# Module_Output_Sockets.net
KiCad netlist of a schematic drawn in Altium Designer
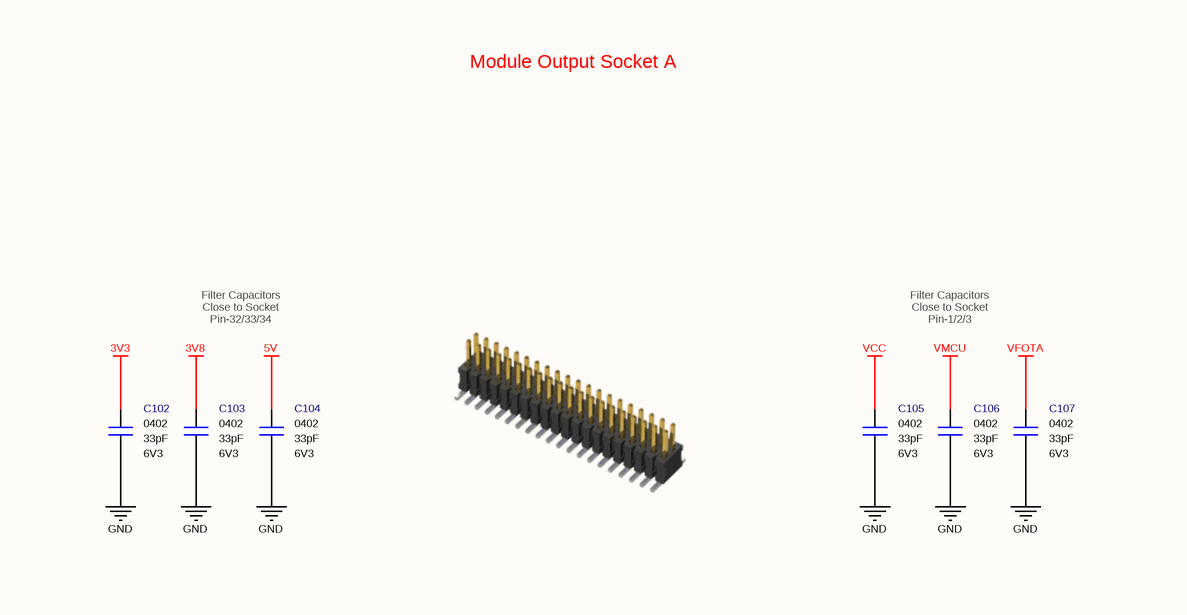
[diagram p0: Module Output Sockets.SchDoc, top left]
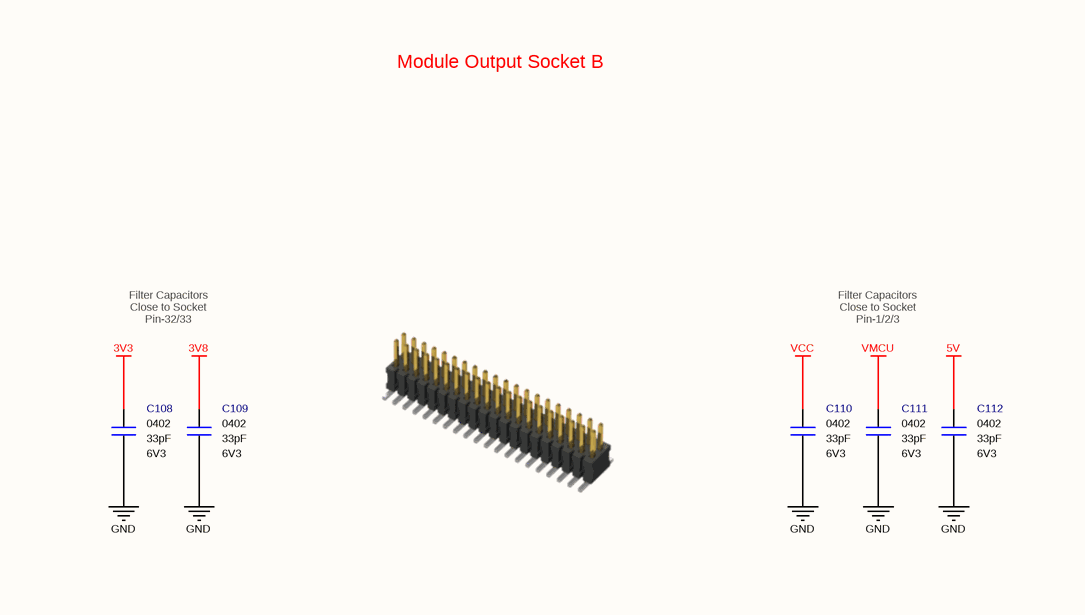
[diagram p1: Module Output Sockets.SchDoc, top right]
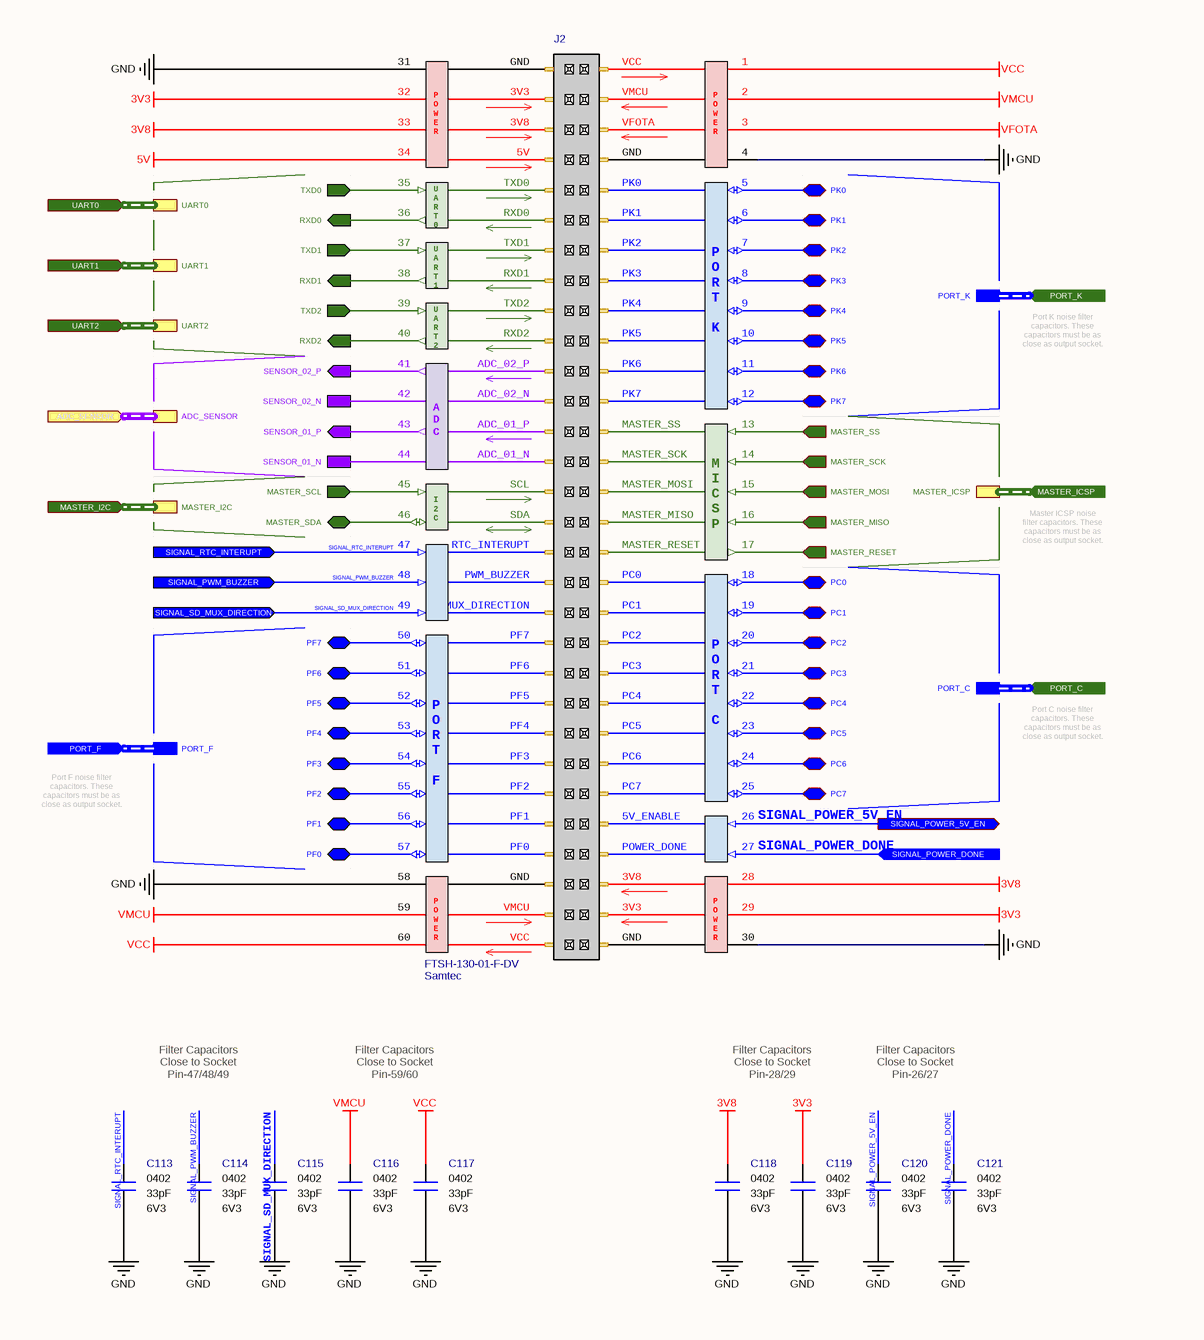
[diagram p2: Module Output Sockets.SchDoc, bottom left]
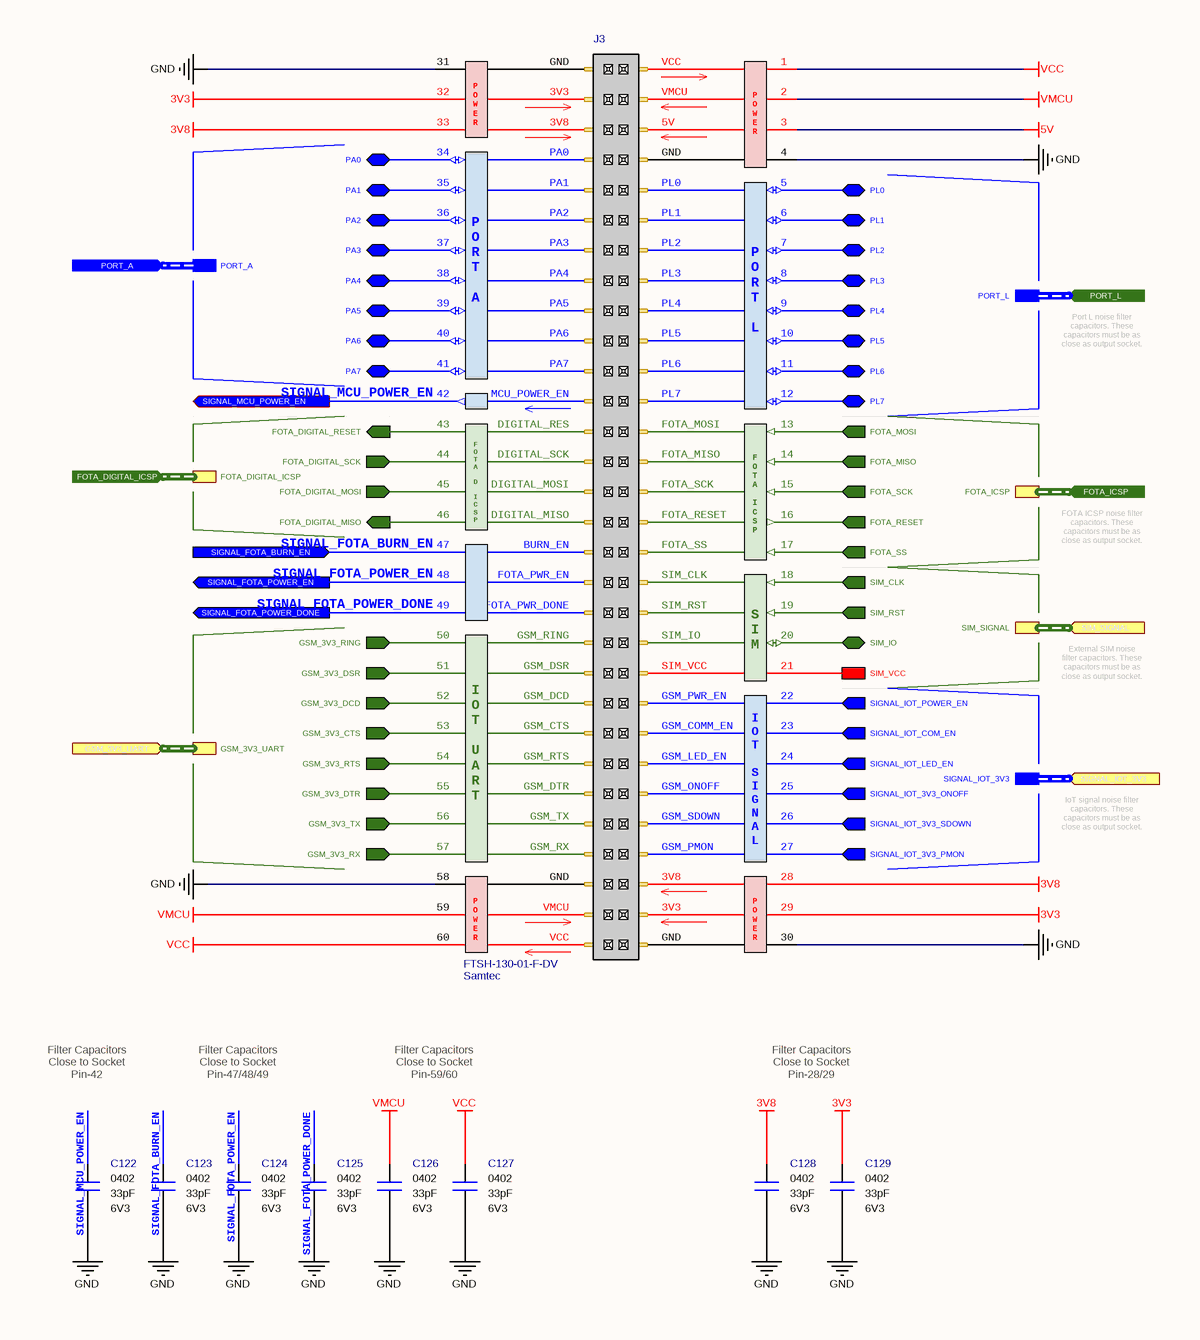
[diagram p3: Module Output Sockets.SchDoc, bottom right]

(export (version "E")
  (design (tool "Eeschema 10.0.6"))
  (components
    (comp (ref "C102")
      (value "33pF")
      (footprint "CAPACITOR_0402")
      (description "Capacitor - 33pF [0402] (Ceramic)")
      (fields
        (field (name "TOLERANCE") "10%")
        (field (name "CASE") "0402")
        (field (name "VOLTAGE") "6V3")
        (field (name "MANUFACTURER PART NUMBER") "C0402C330J9RACAUTO")
      )
      (libsource (lib "Ovoo_Library") (part "Capacitor - 33pF [0402-6V3]"))
    )
    (comp (ref "C103")
      (value "33pF")
      (footprint "CAPACITOR_0402")
      (description "Capacitor - 33pF [0402] (Ceramic)")
      (fields
        (field (name "TOLERANCE") "10%")
        (field (name "CASE") "0402")
        (field (name "VOLTAGE") "6V3")
        (field (name "MANUFACTURER PART NUMBER") "C0402C330J9RACAUTO")
      )
      (libsource (lib "Ovoo_Library") (part "Capacitor - 33pF [0402-6V3]"))
    )
    (comp (ref "C104")
      (value "33pF")
      (footprint "CAPACITOR_0402")
      (description "Capacitor - 33pF [0402] (Ceramic)")
      (fields
        (field (name "TOLERANCE") "10%")
        (field (name "CASE") "0402")
        (field (name "VOLTAGE") "6V3")
        (field (name "MANUFACTURER PART NUMBER") "C0402C330J9RACAUTO")
      )
      (libsource (lib "Ovoo_Library") (part "Capacitor - 33pF [0402-6V3]"))
    )
    (comp (ref "C105")
      (value "33pF")
      (footprint "CAPACITOR_0402")
      (description "Capacitor - 33pF [0402] (Ceramic)")
      (fields
        (field (name "TOLERANCE") "10%")
        (field (name "CASE") "0402")
        (field (name "VOLTAGE") "6V3")
        (field (name "MANUFACTURER PART NUMBER") "C0402C330J9RACAUTO")
      )
      (libsource (lib "Ovoo_Library") (part "Capacitor - 33pF [0402-6V3]"))
    )
    (comp (ref "C106")
      (value "33pF")
      (footprint "CAPACITOR_0402")
      (description "Capacitor - 33pF [0402] (Ceramic)")
      (fields
        (field (name "TOLERANCE") "10%")
        (field (name "CASE") "0402")
        (field (name "VOLTAGE") "6V3")
        (field (name "MANUFACTURER PART NUMBER") "C0402C330J9RACAUTO")
      )
      (libsource (lib "Ovoo_Library") (part "Capacitor - 33pF [0402-6V3]"))
    )
    (comp (ref "C107")
      (value "33pF")
      (footprint "CAPACITOR_0402")
      (description "Capacitor - 33pF [0402] (Ceramic)")
      (fields
        (field (name "TOLERANCE") "10%")
        (field (name "CASE") "0402")
        (field (name "VOLTAGE") "6V3")
        (field (name "MANUFACTURER PART NUMBER") "C0402C330J9RACAUTO")
      )
      (libsource (lib "Ovoo_Library") (part "Capacitor - 33pF [0402-6V3]"))
    )
    (comp (ref "C108")
      (value "33pF")
      (footprint "CAPACITOR_0402")
      (description "Capacitor - 33pF [0402] (Ceramic)")
      (fields
        (field (name "TOLERANCE") "10%")
        (field (name "CASE") "0402")
        (field (name "VOLTAGE") "6V3")
        (field (name "MANUFACTURER PART NUMBER") "C0402C330J9RACAUTO")
      )
      (libsource (lib "Ovoo_Library") (part "Capacitor - 33pF [0402-6V3]"))
    )
    (comp (ref "C109")
      (value "33pF")
      (footprint "CAPACITOR_0402")
      (description "Capacitor - 33pF [0402] (Ceramic)")
      (fields
        (field (name "TOLERANCE") "10%")
        (field (name "CASE") "0402")
        (field (name "VOLTAGE") "6V3")
        (field (name "MANUFACTURER PART NUMBER") "C0402C330J9RACAUTO")
      )
      (libsource (lib "Ovoo_Library") (part "Capacitor - 33pF [0402-6V3]"))
    )
    (comp (ref "C110")
      (value "33pF")
      (footprint "CAPACITOR_0402")
      (description "Capacitor - 33pF [0402] (Ceramic)")
      (fields
        (field (name "TOLERANCE") "10%")
        (field (name "CASE") "0402")
        (field (name "VOLTAGE") "6V3")
        (field (name "MANUFACTURER PART NUMBER") "C0402C330J9RACAUTO")
      )
      (libsource (lib "Ovoo_Library") (part "Capacitor - 33pF [0402-6V3]"))
    )
    (comp (ref "C111")
      (value "33pF")
      (footprint "CAPACITOR_0402")
      (description "Capacitor - 33pF [0402] (Ceramic)")
      (fields
        (field (name "TOLERANCE") "10%")
        (field (name "CASE") "0402")
        (field (name "VOLTAGE") "6V3")
        (field (name "MANUFACTURER PART NUMBER") "C0402C330J9RACAUTO")
      )
      (libsource (lib "Ovoo_Library") (part "Capacitor - 33pF [0402-6V3]"))
    )
    (comp (ref "C112")
      (value "33pF")
      (footprint "CAPACITOR_0402")
      (description "Capacitor - 33pF [0402] (Ceramic)")
      (fields
        (field (name "TOLERANCE") "10%")
        (field (name "CASE") "0402")
        (field (name "VOLTAGE") "6V3")
        (field (name "MANUFACTURER PART NUMBER") "C0402C330J9RACAUTO")
      )
      (libsource (lib "Ovoo_Library") (part "Capacitor - 33pF [0402-6V3]"))
    )
    (comp (ref "C113")
      (value "33pF")
      (footprint "CAPACITOR_0402")
      (description "Capacitor - 33pF [0402] (Ceramic)")
      (fields
        (field (name "TOLERANCE") "10%")
        (field (name "CASE") "0402")
        (field (name "VOLTAGE") "6V3")
        (field (name "MANUFACTURER PART NUMBER") "C0402C330J9RACAUTO")
      )
      (libsource (lib "Ovoo_Library") (part "Capacitor - 33pF [0402-6V3]"))
    )
    (comp (ref "C114")
      (value "33pF")
      (footprint "CAPACITOR_0402")
      (description "Capacitor - 33pF [0402] (Ceramic)")
      (fields
        (field (name "TOLERANCE") "10%")
        (field (name "CASE") "0402")
        (field (name "VOLTAGE") "6V3")
        (field (name "MANUFACTURER PART NUMBER") "C0402C330J9RACAUTO")
      )
      (libsource (lib "Ovoo_Library") (part "Capacitor - 33pF [0402-6V3]"))
    )
    (comp (ref "C115")
      (value "33pF")
      (footprint "CAPACITOR_0402")
      (description "Capacitor - 33pF [0402] (Ceramic)")
      (fields
        (field (name "TOLERANCE") "10%")
        (field (name "CASE") "0402")
        (field (name "VOLTAGE") "6V3")
        (field (name "MANUFACTURER PART NUMBER") "C0402C330J9RACAUTO")
      )
      (libsource (lib "Ovoo_Library") (part "Capacitor - 33pF [0402-6V3]"))
    )
    (comp (ref "C116")
      (value "33pF")
      (footprint "CAPACITOR_0402")
      (description "Capacitor - 33pF [0402] (Ceramic)")
      (fields
        (field (name "TOLERANCE") "10%")
        (field (name "CASE") "0402")
        (field (name "VOLTAGE") "6V3")
        (field (name "MANUFACTURER PART NUMBER") "C0402C330J9RACAUTO")
      )
      (libsource (lib "Ovoo_Library") (part "Capacitor - 33pF [0402-6V3]"))
    )
    (comp (ref "C117")
      (value "33pF")
      (footprint "CAPACITOR_0402")
      (description "Capacitor - 33pF [0402] (Ceramic)")
      (fields
        (field (name "TOLERANCE") "10%")
        (field (name "CASE") "0402")
        (field (name "VOLTAGE") "6V3")
        (field (name "MANUFACTURER PART NUMBER") "C0402C330J9RACAUTO")
      )
      (libsource (lib "Ovoo_Library") (part "Capacitor - 33pF [0402-6V3]"))
    )
    (comp (ref "C118")
      (value "33pF")
      (footprint "CAPACITOR_0402")
      (description "Capacitor - 33pF [0402] (Ceramic)")
      (fields
        (field (name "TOLERANCE") "10%")
        (field (name "CASE") "0402")
        (field (name "VOLTAGE") "6V3")
        (field (name "MANUFACTURER PART NUMBER") "C0402C330J9RACAUTO")
      )
      (libsource (lib "Ovoo_Library") (part "Capacitor - 33pF [0402-6V3]"))
    )
    (comp (ref "C119")
      (value "33pF")
      (footprint "CAPACITOR_0402")
      (description "Capacitor - 33pF [0402] (Ceramic)")
      (fields
        (field (name "TOLERANCE") "10%")
        (field (name "CASE") "0402")
        (field (name "VOLTAGE") "6V3")
        (field (name "MANUFACTURER PART NUMBER") "C0402C330J9RACAUTO")
      )
      (libsource (lib "Ovoo_Library") (part "Capacitor - 33pF [0402-6V3]"))
    )
    (comp (ref "C120")
      (value "33pF")
      (footprint "CAPACITOR_0402")
      (description "Capacitor - 33pF [0402] (Ceramic)")
      (fields
        (field (name "TOLERANCE") "10%")
        (field (name "CASE") "0402")
        (field (name "VOLTAGE") "6V3")
        (field (name "MANUFACTURER PART NUMBER") "C0402C330J9RACAUTO")
      )
      (libsource (lib "Ovoo_Library") (part "Capacitor - 33pF [0402-6V3]"))
    )
    (comp (ref "C121")
      (value "33pF")
      (footprint "CAPACITOR_0402")
      (description "Capacitor - 33pF [0402] (Ceramic)")
      (fields
        (field (name "TOLERANCE") "10%")
        (field (name "CASE") "0402")
        (field (name "VOLTAGE") "6V3")
        (field (name "MANUFACTURER PART NUMBER") "C0402C330J9RACAUTO")
      )
      (libsource (lib "Ovoo_Library") (part "Capacitor - 33pF [0402-6V3]"))
    )
    (comp (ref "C122")
      (value "33pF")
      (footprint "CAPACITOR_0402")
      (description "Capacitor - 33pF [0402] (Ceramic)")
      (fields
        (field (name "TOLERANCE") "10%")
        (field (name "CASE") "0402")
        (field (name "VOLTAGE") "6V3")
        (field (name "MANUFACTURER PART NUMBER") "C0402C330J9RACAUTO")
      )
      (libsource (lib "Ovoo_Library") (part "Capacitor - 33pF [0402-6V3]"))
    )
    (comp (ref "C123")
      (value "33pF")
      (footprint "CAPACITOR_0402")
      (description "Capacitor - 33pF [0402] (Ceramic)")
      (fields
        (field (name "TOLERANCE") "10%")
        (field (name "CASE") "0402")
        (field (name "VOLTAGE") "6V3")
        (field (name "MANUFACTURER PART NUMBER") "C0402C330J9RACAUTO")
      )
      (libsource (lib "Ovoo_Library") (part "Capacitor - 33pF [0402-6V3]"))
    )
    (comp (ref "C124")
      (value "33pF")
      (footprint "CAPACITOR_0402")
      (description "Capacitor - 33pF [0402] (Ceramic)")
      (fields
        (field (name "TOLERANCE") "10%")
        (field (name "CASE") "0402")
        (field (name "VOLTAGE") "6V3")
        (field (name "MANUFACTURER PART NUMBER") "C0402C330J9RACAUTO")
      )
      (libsource (lib "Ovoo_Library") (part "Capacitor - 33pF [0402-6V3]"))
    )
    (comp (ref "C125")
      (value "33pF")
      (footprint "CAPACITOR_0402")
      (description "Capacitor - 33pF [0402] (Ceramic)")
      (fields
        (field (name "TOLERANCE") "10%")
        (field (name "CASE") "0402")
        (field (name "VOLTAGE") "6V3")
        (field (name "MANUFACTURER PART NUMBER") "C0402C330J9RACAUTO")
      )
      (libsource (lib "Ovoo_Library") (part "Capacitor - 33pF [0402-6V3]"))
    )
    (comp (ref "C126")
      (value "33pF")
      (footprint "CAPACITOR_0402")
      (description "Capacitor - 33pF [0402] (Ceramic)")
      (fields
        (field (name "TOLERANCE") "10%")
        (field (name "CASE") "0402")
        (field (name "VOLTAGE") "6V3")
        (field (name "MANUFACTURER PART NUMBER") "C0402C330J9RACAUTO")
      )
      (libsource (lib "Ovoo_Library") (part "Capacitor - 33pF [0402-6V3]"))
    )
    (comp (ref "C127")
      (value "33pF")
      (footprint "CAPACITOR_0402")
      (description "Capacitor - 33pF [0402] (Ceramic)")
      (fields
        (field (name "TOLERANCE") "10%")
        (field (name "CASE") "0402")
        (field (name "VOLTAGE") "6V3")
        (field (name "MANUFACTURER PART NUMBER") "C0402C330J9RACAUTO")
      )
      (libsource (lib "Ovoo_Library") (part "Capacitor - 33pF [0402-6V3]"))
    )
    (comp (ref "C128")
      (value "33pF")
      (footprint "CAPACITOR_0402")
      (description "Capacitor - 33pF [0402] (Ceramic)")
      (fields
        (field (name "TOLERANCE") "10%")
        (field (name "CASE") "0402")
        (field (name "VOLTAGE") "6V3")
        (field (name "MANUFACTURER PART NUMBER") "C0402C330J9RACAUTO")
      )
      (libsource (lib "Ovoo_Library") (part "Capacitor - 33pF [0402-6V3]"))
    )
    (comp (ref "C129")
      (value "33pF")
      (footprint "CAPACITOR_0402")
      (description "Capacitor - 33pF [0402] (Ceramic)")
      (fields
        (field (name "TOLERANCE") "10%")
        (field (name "CASE") "0402")
        (field (name "VOLTAGE") "6V3")
        (field (name "MANUFACTURER PART NUMBER") "C0402C330J9RACAUTO")
      )
      (libsource (lib "Ovoo_Library") (part "Capacitor - 33pF [0402-6V3]"))
    )
    (comp (ref "J2")
      (value "1.27 mm Pitch 2x30P Male Connector")
      (footprint "SAMTEC-FTSH-130-01-X-DV")
      (description "Headers & Wire Housings BREAKAWAY HDR VERT 6")
      (fields
        (field (name "MOUSER PART NUMBER") "200-FTSH13001FDV")
        (field (name "MANUFACTURER PART NUMBER") "FTSH-130-01-F-DV")
        (field (name "MANUFACTURER NAME") "Samtec")
      )
      (libsource (lib "Ovoo_Library") (part "Connector - B100 Male Socket [A]"))
    )
    (comp (ref "J3")
      (value "1.27 mm Pitch 2x30P Male Connector")
      (footprint "SAMTEC-FTSH-130-01-X-DV")
      (description "Headers & Wire Housings BREAKAWAY HDR VERT 6")
      (fields
        (field (name "MOUSER PART NUMBER") "200-FTSH13001FDV")
        (field (name "MANUFACTURER PART NUMBER") "FTSH-130-01-F-DV")
        (field (name "MANUFACTURER NAME") "Samtec")
      )
      (libsource (lib "Ovoo_Library") (part "Connector - B100 Male Socket [B]"))
    )
  )
  (nets
    (net (code "19") (name "/FOTA_DIGITAL_MISO") (class "Default")
      (node (ref "J3") (pin "46") (pinfunction "Pin-46_46") (pintype "passive"))
    )
    (net (code "20") (name "/FOTA_DIGITAL_MOSI") (class "Default")
      (node (ref "J3") (pin "45") (pinfunction "Pin-45_45") (pintype "passive"))
    )
    (net (code "21") (name "/FOTA_DIGITAL_RESET") (class "Default")
      (node (ref "J3") (pin "43") (pinfunction "Pin-43_43") (pintype "passive"))
    )
    (net (code "22") (name "/FOTA_DIGITAL_SCK") (class "Default")
      (node (ref "J3") (pin "44") (pinfunction "Pin-44_44") (pintype "passive"))
    )
    (net (code "24") (name "/FOTA_MISO") (class "Default")
      (node (ref "J3") (pin "14") (pinfunction "Pin-14_14") (pintype "input"))
    )
    (net (code "25") (name "/FOTA_MOSI") (class "Default")
      (node (ref "J3") (pin "13") (pinfunction "Pin-13_13") (pintype "input"))
    )
    (net (code "26") (name "/FOTA_RESET") (class "Default")
      (node (ref "J3") (pin "16") (pinfunction "Pin-16_16") (pintype "output"))
    )
    (net (code "27") (name "/FOTA_SCK") (class "Default")
      (node (ref "J3") (pin "15") (pinfunction "Pin-15_15") (pintype "input"))
    )
    (net (code "28") (name "/FOTA_SS") (class "Default")
      (node (ref "J3") (pin "17") (pinfunction "Pin-17_17") (pintype "input"))
    )
    (net (code "29") (name "/GSM_3V3_CTS") (class "Default")
      (node (ref "J3") (pin "53") (pinfunction "Pin-53_53") (pintype "passive"))
    )
    (net (code "30") (name "/GSM_3V3_DCD") (class "Default")
      (node (ref "J3") (pin "52") (pinfunction "Pin-52_52") (pintype "passive"))
    )
    (net (code "31") (name "/GSM_3V3_DSR") (class "Default")
      (node (ref "J3") (pin "51") (pinfunction "Pin-51_51") (pintype "passive"))
    )
    (net (code "32") (name "/GSM_3V3_DTR") (class "Default")
      (node (ref "J3") (pin "55") (pinfunction "Pin-55_55") (pintype "passive"))
    )
    (net (code "33") (name "/GSM_3V3_RING") (class "Default")
      (node (ref "J3") (pin "50") (pinfunction "Pin-50_50") (pintype "passive"))
    )
    (net (code "34") (name "/GSM_3V3_RTS") (class "Default")
      (node (ref "J3") (pin "54") (pinfunction "Pin-54_54") (pintype "passive"))
    )
    (net (code "35") (name "/GSM_3V3_RX") (class "Default")
      (node (ref "J3") (pin "57") (pinfunction "Pin-57_57") (pintype "passive"))
    )
    (net (code "36") (name "/GSM_3V3_TX") (class "Default")
      (node (ref "J3") (pin "56") (pinfunction "Pin-56_56") (pintype "passive"))
    )
    (net (code "40") (name "/MASTER_MISO") (class "Default")
      (node (ref "J2") (pin "16") (pinfunction "Pin-16_16") (pintype "input"))
    )
    (net (code "41") (name "/MASTER_MOSI") (class "Default")
      (node (ref "J2") (pin "15") (pinfunction "Pin-15_15") (pintype "input"))
    )
    (net (code "42") (name "/MASTER_RESET") (class "Default")
      (node (ref "J2") (pin "17") (pinfunction "Pin-17_17") (pintype "output"))
    )
    (net (code "43") (name "/MASTER_SCK") (class "Default")
      (node (ref "J2") (pin "14") (pinfunction "Pin-14_14") (pintype "input"))
    )
    (net (code "44") (name "/MASTER_SCL") (class "Default")
      (node (ref "J2") (pin "45") (pinfunction "Pin-45_45") (pintype "input"))
    )
    (net (code "45") (name "/MASTER_SDA") (class "Default")
      (node (ref "J2") (pin "46") (pinfunction "Pin-46_46") (pintype "bidirectional"))
    )
    (net (code "46") (name "/MASTER_SS") (class "Default")
      (node (ref "J2") (pin "13") (pinfunction "Pin-13_13") (pintype "input"))
    )
    (net (code "47") (name "/PA0") (class "Default")
      (node (ref "J3") (pin "34") (pinfunction "Pin-34_34") (pintype "bidirectional"))
    )
    (net (code "48") (name "/PA1") (class "Default")
      (node (ref "J3") (pin "35") (pinfunction "Pin-35_35") (pintype "bidirectional"))
    )
    (net (code "49") (name "/PA2") (class "Default")
      (node (ref "J3") (pin "36") (pinfunction "Pin-36_36") (pintype "bidirectional"))
    )
    (net (code "50") (name "/PA3") (class "Default")
      (node (ref "J3") (pin "37") (pinfunction "Pin-37_37") (pintype "bidirectional"))
    )
    (net (code "51") (name "/PA4") (class "Default")
      (node (ref "J3") (pin "38") (pinfunction "Pin-38_38") (pintype "bidirectional"))
    )
    (net (code "52") (name "/PA5") (class "Default")
      (node (ref "J3") (pin "39") (pinfunction "Pin-39_39") (pintype "bidirectional"))
    )
    (net (code "53") (name "/PA6") (class "Default")
      (node (ref "J3") (pin "40") (pinfunction "Pin-40_40") (pintype "bidirectional"))
    )
    (net (code "54") (name "/PA7") (class "Default")
      (node (ref "J3") (pin "41") (pinfunction "Pin-41_41") (pintype "bidirectional"))
    )
    (net (code "55") (name "/PC0") (class "Default")
      (node (ref "J2") (pin "18") (pinfunction "Pin-18_18") (pintype "bidirectional"))
    )
    (net (code "56") (name "/PC1") (class "Default")
      (node (ref "J2") (pin "19") (pinfunction "Pin-19_19") (pintype "bidirectional"))
    )
    (net (code "57") (name "/PC2") (class "Default")
      (node (ref "J2") (pin "20") (pinfunction "Pin-20_20") (pintype "bidirectional"))
    )
    (net (code "58") (name "/PC3") (class "Default")
      (node (ref "J2") (pin "21") (pinfunction "Pin-21_21") (pintype "bidirectional"))
    )
    (net (code "59") (name "/PC4") (class "Default")
      (node (ref "J2") (pin "22") (pinfunction "Pin-22_22") (pintype "bidirectional"))
    )
    (net (code "60") (name "/PC5") (class "Default")
      (node (ref "J2") (pin "23") (pinfunction "Pin-23_23") (pintype "bidirectional"))
    )
    (net (code "61") (name "/PC6") (class "Default")
      (node (ref "J2") (pin "24") (pinfunction "Pin-24_24") (pintype "bidirectional"))
    )
    (net (code "62") (name "/PC7") (class "Default")
      (node (ref "J2") (pin "25") (pinfunction "Pin-25_25") (pintype "bidirectional"))
    )
    (net (code "63") (name "/PF0") (class "Default")
      (node (ref "J2") (pin "57") (pinfunction "Pin-57_57") (pintype "bidirectional"))
    )
    (net (code "64") (name "/PF1") (class "Default")
      (node (ref "J2") (pin "56") (pinfunction "Pin-56_56") (pintype "bidirectional"))
    )
    (net (code "65") (name "/PF2") (class "Default")
      (node (ref "J2") (pin "55") (pinfunction "Pin-55_55") (pintype "bidirectional"))
    )
    (net (code "66") (name "/PF3") (class "Default")
      (node (ref "J2") (pin "54") (pinfunction "Pin-54_54") (pintype "bidirectional"))
    )
    (net (code "67") (name "/PF4") (class "Default")
      (node (ref "J2") (pin "53") (pinfunction "Pin-53_53") (pintype "bidirectional"))
    )
    (net (code "68") (name "/PF5") (class "Default")
      (node (ref "J2") (pin "52") (pinfunction "Pin-52_52") (pintype "bidirectional"))
    )
    (net (code "69") (name "/PF6") (class "Default")
      (node (ref "J2") (pin "51") (pinfunction "Pin-51_51") (pintype "bidirectional"))
    )
    (net (code "70") (name "/PF7") (class "Default")
      (node (ref "J2") (pin "50") (pinfunction "Pin-50_50") (pintype "bidirectional"))
    )
    (net (code "71") (name "/PK0") (class "Default")
      (node (ref "J2") (pin "5") (pinfunction "Pin-5_5") (pintype "bidirectional"))
    )
    (net (code "72") (name "/PK1") (class "Default")
      (node (ref "J2") (pin "6") (pinfunction "Pin-6_6") (pintype "bidirectional"))
    )
    (net (code "73") (name "/PK2") (class "Default")
      (node (ref "J2") (pin "7") (pinfunction "Pin-7_7") (pintype "bidirectional"))
    )
    (net (code "74") (name "/PK3") (class "Default")
      (node (ref "J2") (pin "8") (pinfunction "Pin-8_8") (pintype "bidirectional"))
    )
    (net (code "75") (name "/PK4") (class "Default")
      (node (ref "J2") (pin "9") (pinfunction "Pin-9_9") (pintype "bidirectional"))
    )
    (net (code "76") (name "/PK5") (class "Default")
      (node (ref "J2") (pin "10") (pinfunction "Pin-10_10") (pintype "bidirectional"))
    )
    (net (code "77") (name "/PK6") (class "Default")
      (node (ref "J2") (pin "11") (pinfunction "Pin-11_11") (pintype "bidirectional"))
    )
    (net (code "78") (name "/PK7") (class "Default")
      (node (ref "J2") (pin "12") (pinfunction "Pin-12_12") (pintype "bidirectional"))
    )
    (net (code "79") (name "/PL0") (class "Default")
      (node (ref "J3") (pin "5") (pinfunction "Pin-5_5") (pintype "bidirectional"))
    )
    (net (code "80") (name "/PL1") (class "Default")
      (node (ref "J3") (pin "6") (pinfunction "Pin-6_6") (pintype "bidirectional"))
    )
    (net (code "81") (name "/PL2") (class "Default")
      (node (ref "J3") (pin "7") (pinfunction "Pin-7_7") (pintype "bidirectional"))
    )
    (net (code "82") (name "/PL3") (class "Default")
      (node (ref "J3") (pin "8") (pinfunction "Pin-8_8") (pintype "bidirectional"))
    )
    (net (code "83") (name "/PL4") (class "Default")
      (node (ref "J3") (pin "9") (pinfunction "Pin-9_9") (pintype "bidirectional"))
    )
    (net (code "84") (name "/PL5") (class "Default")
      (node (ref "J3") (pin "10") (pinfunction "Pin-10_10") (pintype "bidirectional"))
    )
    (net (code "85") (name "/PL6") (class "Default")
      (node (ref "J3") (pin "11") (pinfunction "Pin-11_11") (pintype "bidirectional"))
    )
    (net (code "86") (name "/PL7") (class "Default")
      (node (ref "J3") (pin "12") (pinfunction "Pin-12_12") (pintype "bidirectional"))
    )
    (net (code "92") (name "/RXD0") (class "Default")
      (node (ref "J2") (pin "36") (pinfunction "Pin-36_36") (pintype "output"))
    )
    (net (code "93") (name "/RXD1") (class "Default")
      (node (ref "J2") (pin "38") (pinfunction "Pin-38_38") (pintype "output"))
    )
    (net (code "94") (name "/RXD2") (class "Default")
      (node (ref "J2") (pin "40") (pinfunction "Pin-40_40") (pintype "output"))
    )
    (net (code "95") (name "/SENSOR_01_N") (class "Default")
      (node (ref "J2") (pin "44") (pinfunction "Pin-44_44") (pintype "passive"))
    )
    (net (code "96") (name "/SENSOR_01_P") (class "Default")
      (node (ref "J2") (pin "43") (pinfunction "Pin-43_43") (pintype "output"))
    )
    (net (code "97") (name "/SENSOR_02_N") (class "Default")
      (node (ref "J2") (pin "42") (pinfunction "Pin-42_42") (pintype "passive"))
    )
    (net (code "98") (name "/SENSOR_02_P") (class "Default")
      (node (ref "J2") (pin "41") (pinfunction "Pin-41_41") (pintype "output"))
    )
    (net (code "99") (name "/SIGNAL_FOTA_BURN_EN") (class "Default")
      (node (ref "C123") (pin "2") (pinfunction "2_2") (pintype "passive"))
      (node (ref "J3") (pin "47") (pinfunction "Pin-47_47") (pintype "passive"))
    )
    (net (code "100") (name "/SIGNAL_FOTA_POWER_DONE") (class "Default")
      (node (ref "C125") (pin "2") (pinfunction "2_2") (pintype "passive"))
      (node (ref "J3") (pin "49") (pinfunction "Pin-49_49") (pintype "passive"))
    )
    (net (code "101") (name "/SIGNAL_FOTA_POWER_EN") (class "Default")
      (node (ref "C124") (pin "2") (pinfunction "2_2") (pintype "passive"))
      (node (ref "J3") (pin "48") (pinfunction "Pin-48_48") (pintype "passive"))
    )
    (net (code "102") (name "/SIGNAL_IOT_3V3_ONOFF") (class "Default")
      (node (ref "J3") (pin "25") (pinfunction "Pin-25_25") (pintype "passive"))
    )
    (net (code "103") (name "/SIGNAL_IOT_3V3_PMON") (class "Default")
      (node (ref "J3") (pin "27") (pinfunction "Pin-27_27") (pintype "passive"))
    )
    (net (code "104") (name "/SIGNAL_IOT_3V3_SDOWN") (class "Default")
      (node (ref "J3") (pin "26") (pinfunction "Pin-26_26") (pintype "passive"))
    )
    (net (code "106") (name "/SIGNAL_IOT_COM_EN") (class "Default")
      (node (ref "J3") (pin "23") (pinfunction "Pin-23_23") (pintype "passive"))
    )
    (net (code "107") (name "/SIGNAL_IOT_LED_EN") (class "Default")
      (node (ref "J3") (pin "24") (pinfunction "Pin-24_24") (pintype "passive"))
    )
    (net (code "108") (name "/SIGNAL_IOT_POWER_EN") (class "Default")
      (node (ref "J3") (pin "22") (pinfunction "Pin-22_22") (pintype "passive"))
    )
    (net (code "109") (name "/SIGNAL_MCU_POWER_EN") (class "Default")
      (node (ref "C122") (pin "2") (pinfunction "2_2") (pintype "passive"))
      (node (ref "J3") (pin "42") (pinfunction "Pin-42_42") (pintype "output"))
    )
    (net (code "110") (name "/SIGNAL_POWER_5V_EN") (class "Default")
      (node (ref "C120") (pin "2") (pinfunction "2_2") (pintype "passive"))
      (node (ref "J2") (pin "26") (pinfunction "Pin-26_26") (pintype "input"))
    )
    (net (code "111") (name "/SIGNAL_POWER_DONE") (class "Default")
      (node (ref "C121") (pin "2") (pinfunction "2_2") (pintype "passive"))
      (node (ref "J2") (pin "27") (pinfunction "Pin-27_27") (pintype "input"))
    )
    (net (code "112") (name "/SIGNAL_PWM_BUZZER") (class "Default")
      (node (ref "C114") (pin "2") (pinfunction "2_2") (pintype "passive"))
      (node (ref "J2") (pin "48") (pinfunction "Pin-48_48") (pintype "input"))
    )
    (net (code "113") (name "/SIGNAL_RTC_INTERUPT") (class "Default")
      (node (ref "C113") (pin "2") (pinfunction "2_2") (pintype "passive"))
      (node (ref "J2") (pin "47") (pinfunction "Pin-47_47") (pintype "input"))
    )
    (net (code "114") (name "/SIGNAL_SD_MUX_DIRECTION") (class "Default")
      (node (ref "C115") (pin "2") (pinfunction "2_2") (pintype "passive"))
      (node (ref "J2") (pin "49") (pinfunction "Pin-49_49") (pintype "input"))
    )
    (net (code "115") (name "/SIM_CLK") (class "Default")
      (node (ref "J3") (pin "18") (pinfunction "Pin-18_18") (pintype "input"))
    )
    (net (code "116") (name "/SIM_IO") (class "Default")
      (node (ref "J3") (pin "20") (pinfunction "Pin-20_20") (pintype "bidirectional"))
    )
    (net (code "117") (name "/SIM_RST") (class "Default")
      (node (ref "J3") (pin "19") (pinfunction "Pin-19_19") (pintype "input"))
    )
    (net (code "119") (name "/SIM_VCC") (class "Default")
      (node (ref "J3") (pin "21") (pinfunction "Pin-21_21") (pintype "power_in"))
    )
    (net (code "120") (name "/TXD0") (class "Default")
      (node (ref "J2") (pin "35") (pinfunction "Pin-35_35") (pintype "input"))
    )
    (net (code "121") (name "/TXD1") (class "Default")
      (node (ref "J2") (pin "37") (pinfunction "Pin-37_37") (pintype "input"))
    )
    (net (code "122") (name "/TXD2") (class "Default")
      (node (ref "J2") (pin "39") (pinfunction "Pin-39_39") (pintype "input"))
    )
    (net (code "126") (name "3V3") (class "Default")
      (node (ref "C102") (pin "2") (pinfunction "2_2") (pintype "passive"))
      (node (ref "C108") (pin "2") (pinfunction "2_2") (pintype "passive"))
      (node (ref "C119") (pin "2") (pinfunction "2_2") (pintype "passive"))
      (node (ref "C129") (pin "2") (pinfunction "2_2") (pintype "passive"))
      (node (ref "J2") (pin "29") (pinfunction "Pin-29_29") (pintype "passive"))
      (node (ref "J2") (pin "32") (pinfunction "Pin-32_32") (pintype "power_in"))
      (node (ref "J3") (pin "29") (pinfunction "Pin-29_29") (pintype "power_in"))
      (node (ref "J3") (pin "32") (pinfunction "Pin-32_32") (pintype "power_in"))
    )
    (net (code "127") (name "3V8") (class "Default")
      (node (ref "C103") (pin "2") (pinfunction "2_2") (pintype "passive"))
      (node (ref "C109") (pin "2") (pinfunction "2_2") (pintype "passive"))
      (node (ref "C118") (pin "2") (pinfunction "2_2") (pintype "passive"))
      (node (ref "C128") (pin "2") (pinfunction "2_2") (pintype "passive"))
      (node (ref "J2") (pin "28") (pinfunction "Pin-28_28") (pintype "passive"))
      (node (ref "J2") (pin "33") (pinfunction "Pin-33_33") (pintype "power_in"))
      (node (ref "J3") (pin "28") (pinfunction "Pin-28_28") (pintype "power_in"))
      (node (ref "J3") (pin "33") (pinfunction "Pin-33_33") (pintype "power_in"))
    )
    (net (code "128") (name "5V") (class "Default")
      (node (ref "C104") (pin "2") (pinfunction "2_2") (pintype "passive"))
      (node (ref "C112") (pin "2") (pinfunction "2_2") (pintype "passive"))
      (node (ref "J2") (pin "34") (pinfunction "Pin-34_34") (pintype "power_in"))
      (node (ref "J3") (pin "3") (pinfunction "Pin-3_3") (pintype "power_in"))
    )
    (net (code "129") (name "GND") (class "Default")
      (node (ref "C102") (pin "1") (pinfunction "1_1") (pintype "passive"))
      (node (ref "C103") (pin "1") (pinfunction "1_1") (pintype "passive"))
      (node (ref "C104") (pin "1") (pinfunction "1_1") (pintype "passive"))
      (node (ref "C105") (pin "1") (pinfunction "1_1") (pintype "passive"))
      (node (ref "C106") (pin "1") (pinfunction "1_1") (pintype "passive"))
      (node (ref "C107") (pin "1") (pinfunction "1_1") (pintype "passive"))
      (node (ref "C108") (pin "1") (pinfunction "1_1") (pintype "passive"))
      (node (ref "C109") (pin "1") (pinfunction "1_1") (pintype "passive"))
      (node (ref "C110") (pin "1") (pinfunction "1_1") (pintype "passive"))
      (node (ref "C111") (pin "1") (pinfunction "1_1") (pintype "passive"))
      (node (ref "C112") (pin "1") (pinfunction "1_1") (pintype "passive"))
      (node (ref "C113") (pin "1") (pinfunction "1_1") (pintype "passive"))
      (node (ref "C114") (pin "1") (pinfunction "1_1") (pintype "passive"))
      (node (ref "C115") (pin "1") (pinfunction "1_1") (pintype "passive"))
      (node (ref "C116") (pin "1") (pinfunction "1_1") (pintype "passive"))
      (node (ref "C117") (pin "1") (pinfunction "1_1") (pintype "passive"))
      (node (ref "C118") (pin "1") (pinfunction "1_1") (pintype "passive"))
      (node (ref "C119") (pin "1") (pinfunction "1_1") (pintype "passive"))
      (node (ref "C120") (pin "1") (pinfunction "1_1") (pintype "passive"))
      (node (ref "C121") (pin "1") (pinfunction "1_1") (pintype "passive"))
      (node (ref "C122") (pin "1") (pinfunction "1_1") (pintype "passive"))
      (node (ref "C123") (pin "1") (pinfunction "1_1") (pintype "passive"))
      (node (ref "C124") (pin "1") (pinfunction "1_1") (pintype "passive"))
      (node (ref "C125") (pin "1") (pinfunction "1_1") (pintype "passive"))
      (node (ref "C126") (pin "1") (pinfunction "1_1") (pintype "passive"))
      (node (ref "C127") (pin "1") (pinfunction "1_1") (pintype "passive"))
      (node (ref "C128") (pin "1") (pinfunction "1_1") (pintype "passive"))
      (node (ref "C129") (pin "1") (pinfunction "1_1") (pintype "passive"))
      (node (ref "J2") (pin "30") (pinfunction "Pin-30_30") (pintype "passive"))
      (node (ref "J2") (pin "31") (pinfunction "Pin-31_31") (pintype "power_in"))
      (node (ref "J2") (pin "4") (pinfunction "Pin-4_4") (pintype "power_in"))
      (node (ref "J2") (pin "58") (pinfunction "Pin-58_58") (pintype "power_in"))
      (node (ref "J3") (pin "30") (pinfunction "Pin-30_30") (pintype "power_in"))
      (node (ref "J3") (pin "31") (pinfunction "Pin-31_31") (pintype "power_in"))
      (node (ref "J3") (pin "4") (pinfunction "Pin-4_4") (pintype "power_in"))
      (node (ref "J3") (pin "58") (pinfunction "Pin-58_58") (pintype "power_in"))
    )
    (net (code "130") (name "VCC") (class "Default")
      (node (ref "C105") (pin "2") (pinfunction "2_2") (pintype "passive"))
      (node (ref "C110") (pin "2") (pinfunction "2_2") (pintype "passive"))
      (node (ref "C117") (pin "2") (pinfunction "2_2") (pintype "passive"))
      (node (ref "C127") (pin "2") (pinfunction "2_2") (pintype "passive"))
      (node (ref "J2") (pin "1") (pinfunction "Pin-1_1") (pintype "power_in"))
      (node (ref "J2") (pin "60") (pinfunction "Pin-60_60") (pintype "power_in"))
      (node (ref "J3") (pin "1") (pinfunction "Pin-1_1") (pintype "power_in"))
      (node (ref "J3") (pin "60") (pinfunction "Pin-60_60") (pintype "power_in"))
    )
    (net (code "131") (name "VFOTA") (class "Default")
      (node (ref "C107") (pin "2") (pinfunction "2_2") (pintype "passive"))
      (node (ref "J2") (pin "3") (pinfunction "Pin-3_3") (pintype "power_in"))
    )
    (net (code "132") (name "VMCU") (class "Default")
      (node (ref "C106") (pin "2") (pinfunction "2_2") (pintype "passive"))
      (node (ref "C111") (pin "2") (pinfunction "2_2") (pintype "passive"))
      (node (ref "C116") (pin "2") (pinfunction "2_2") (pintype "passive"))
      (node (ref "C126") (pin "2") (pinfunction "2_2") (pintype "passive"))
      (node (ref "J2") (pin "2") (pinfunction "Pin-2_2") (pintype "power_in"))
      (node (ref "J2") (pin "59") (pinfunction "Pin-59_59") (pintype "power_in"))
      (node (ref "J3") (pin "2") (pinfunction "Pin-2_2") (pintype "power_in"))
      (node (ref "J3") (pin "59") (pinfunction "Pin-59_59") (pintype "power_in"))
    )
  )
)
